# mainboard.net
KiCad netlist of a schematic drawn in EAGLE
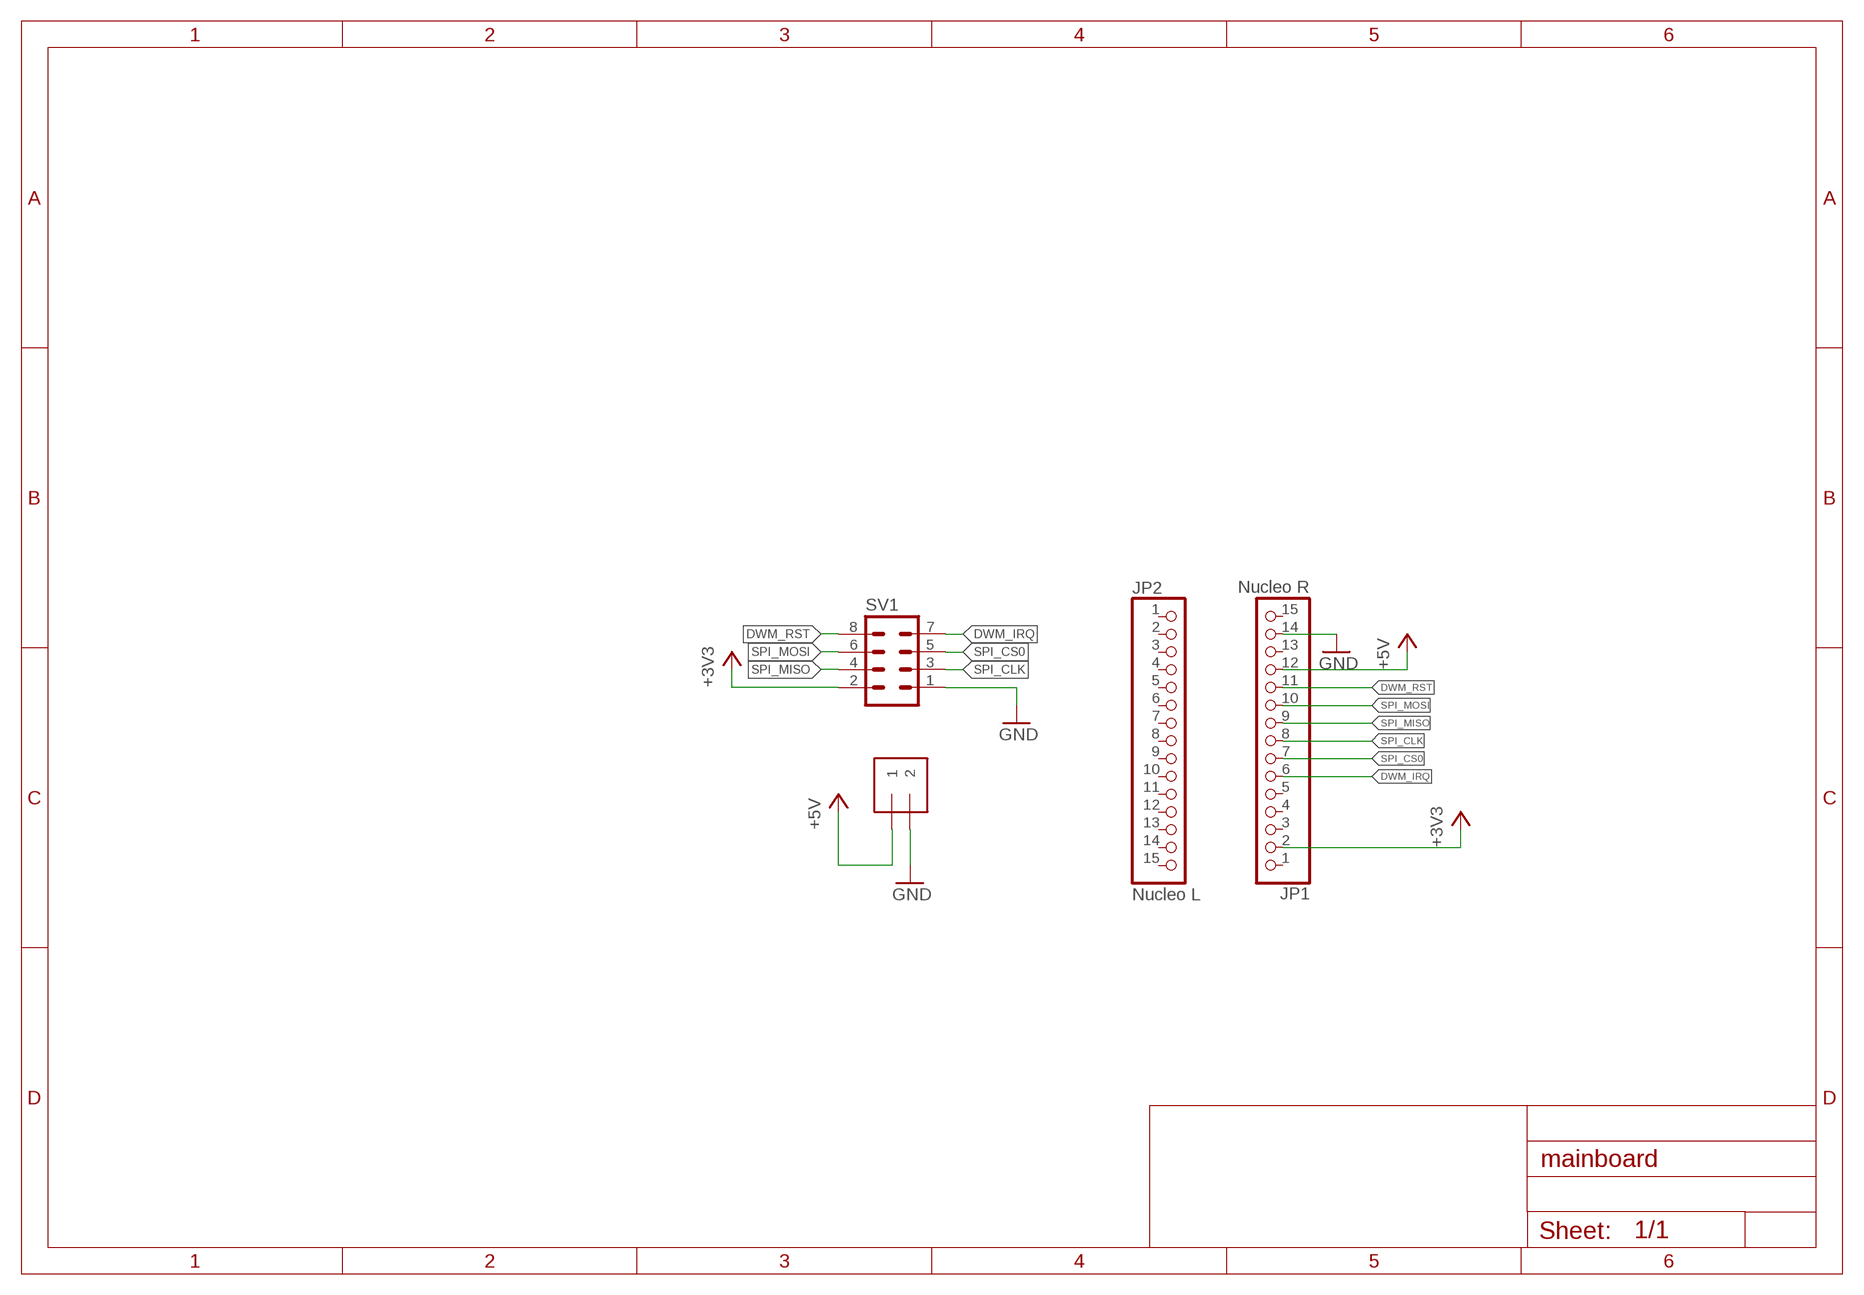
[diagram p0: schematic, sheet 1]

(export (version "E")
  (design (tool "Eeschema 10.0.6"))
  (components
    (comp (ref "J1")
      (value "1X2-3.5MM")
      (footprint "eagle-import:1X2-3.5MM")
      (libsource (lib "eagle-import") (part "1X2-3.5MM"))
    )
    (comp (ref "JP1")
      (value "Nucleo R")
      (footprint "eagle-import:1X15")
      (libsource (lib "eagle-import") (part "PINHD-1X15"))
    )
    (comp (ref "JP2")
      (value "Nucleo L")
      (footprint "eagle-import:1X15")
      (libsource (lib "eagle-import") (part "PINHD-1X15"))
    )
    (comp (ref "SV1")
      (value "MA04-2")
      (footprint "eagle-import:MA04-2")
      (libsource (lib "eagle-import") (part "MA04-2"))
    )
  )
  (nets
    (net (code "1") (name "+3V3") (class "Default")
      (node (ref "JP1") (pin "2") (pinfunction "2_2") (pintype "passive"))
      (node (ref "SV1") (pin "2") (pinfunction "2_2") (pintype "passive"))
    )
    (net (code "2") (name "+5V") (class "Default")
      (node (ref "J1") (pin "1") (pinfunction "1_1") (pintype "passive"))
      (node (ref "JP1") (pin "12") (pinfunction "12_12") (pintype "passive"))
    )
    (net (code "3") (name "DWM_IRQ") (class "Default")
      (node (ref "JP1") (pin "6") (pinfunction "6_6") (pintype "passive"))
      (node (ref "SV1") (pin "7") (pinfunction "7_7") (pintype "passive"))
    )
    (net (code "4") (name "DWM_RST") (class "Default")
      (node (ref "JP1") (pin "11") (pinfunction "11_11") (pintype "passive"))
      (node (ref "SV1") (pin "8") (pinfunction "8_8") (pintype "passive"))
    )
    (net (code "5") (name "GND") (class "Default")
      (node (ref "J1") (pin "2") (pinfunction "2_2") (pintype "passive"))
      (node (ref "JP1") (pin "14") (pinfunction "14_14") (pintype "passive"))
      (node (ref "SV1") (pin "1") (pinfunction "1_1") (pintype "passive"))
    )
    (net (code "6") (name "SPI_CLK") (class "Default")
      (node (ref "JP1") (pin "8") (pinfunction "8_8") (pintype "passive"))
      (node (ref "SV1") (pin "3") (pinfunction "3_3") (pintype "passive"))
    )
    (net (code "7") (name "SPI_CS0") (class "Default")
      (node (ref "JP1") (pin "7") (pinfunction "7_7") (pintype "passive"))
      (node (ref "SV1") (pin "5") (pinfunction "5_5") (pintype "passive"))
    )
    (net (code "8") (name "SPI_MISO") (class "Default")
      (node (ref "JP1") (pin "9") (pinfunction "9_9") (pintype "passive"))
      (node (ref "SV1") (pin "4") (pinfunction "4_4") (pintype "passive"))
    )
    (net (code "9") (name "SPI_MOSI") (class "Default")
      (node (ref "JP1") (pin "10") (pinfunction "10_10") (pintype "passive"))
      (node (ref "SV1") (pin "6") (pinfunction "6_6") (pintype "passive"))
    )
    (net (code "10") (name "unconnected-(JP1-Pad1)") (class "Default")
      (node (ref "JP1") (pin "1") (pinfunction "1_1") (pintype "passive"))
    )
    (net (code "11") (name "unconnected-(JP1-Pad3)") (class "Default")
      (node (ref "JP1") (pin "3") (pinfunction "3_3") (pintype "passive"))
    )
    (net (code "12") (name "unconnected-(JP1-Pad4)") (class "Default")
      (node (ref "JP1") (pin "4") (pinfunction "4_4") (pintype "passive"))
    )
    (net (code "13") (name "unconnected-(JP1-Pad5)") (class "Default")
      (node (ref "JP1") (pin "5") (pinfunction "5_5") (pintype "passive"))
    )
    (net (code "14") (name "unconnected-(JP1-Pad13)") (class "Default")
      (node (ref "JP1") (pin "13") (pinfunction "13_13") (pintype "passive"))
    )
    (net (code "15") (name "unconnected-(JP1-Pad15)") (class "Default")
      (node (ref "JP1") (pin "15") (pinfunction "15_15") (pintype "passive"))
    )
    (net (code "16") (name "unconnected-(JP2-Pad1)") (class "Default")
      (node (ref "JP2") (pin "1") (pinfunction "1_1") (pintype "passive"))
    )
    (net (code "17") (name "unconnected-(JP2-Pad2)") (class "Default")
      (node (ref "JP2") (pin "2") (pinfunction "2_2") (pintype "passive"))
    )
    (net (code "18") (name "unconnected-(JP2-Pad3)") (class "Default")
      (node (ref "JP2") (pin "3") (pinfunction "3_3") (pintype "passive"))
    )
    (net (code "19") (name "unconnected-(JP2-Pad4)") (class "Default")
      (node (ref "JP2") (pin "4") (pinfunction "4_4") (pintype "passive"))
    )
    (net (code "20") (name "unconnected-(JP2-Pad5)") (class "Default")
      (node (ref "JP2") (pin "5") (pinfunction "5_5") (pintype "passive"))
    )
    (net (code "21") (name "unconnected-(JP2-Pad6)") (class "Default")
      (node (ref "JP2") (pin "6") (pinfunction "6_6") (pintype "passive"))
    )
    (net (code "22") (name "unconnected-(JP2-Pad7)") (class "Default")
      (node (ref "JP2") (pin "7") (pinfunction "7_7") (pintype "passive"))
    )
    (net (code "23") (name "unconnected-(JP2-Pad8)") (class "Default")
      (node (ref "JP2") (pin "8") (pinfunction "8_8") (pintype "passive"))
    )
    (net (code "24") (name "unconnected-(JP2-Pad9)") (class "Default")
      (node (ref "JP2") (pin "9") (pinfunction "9_9") (pintype "passive"))
    )
    (net (code "25") (name "unconnected-(JP2-Pad10)") (class "Default")
      (node (ref "JP2") (pin "10") (pinfunction "10_10") (pintype "passive"))
    )
    (net (code "26") (name "unconnected-(JP2-Pad11)") (class "Default")
      (node (ref "JP2") (pin "11") (pinfunction "11_11") (pintype "passive"))
    )
    (net (code "27") (name "unconnected-(JP2-Pad12)") (class "Default")
      (node (ref "JP2") (pin "12") (pinfunction "12_12") (pintype "passive"))
    )
    (net (code "28") (name "unconnected-(JP2-Pad13)") (class "Default")
      (node (ref "JP2") (pin "13") (pinfunction "13_13") (pintype "passive"))
    )
    (net (code "29") (name "unconnected-(JP2-Pad14)") (class "Default")
      (node (ref "JP2") (pin "14") (pinfunction "14_14") (pintype "passive"))
    )
    (net (code "30") (name "unconnected-(JP2-Pad15)") (class "Default")
      (node (ref "JP2") (pin "15") (pinfunction "15_15") (pintype "passive"))
    )
  )
)
